# PCB_Schematic.net
KiCad netlist of a schematic drawn in EAGLE
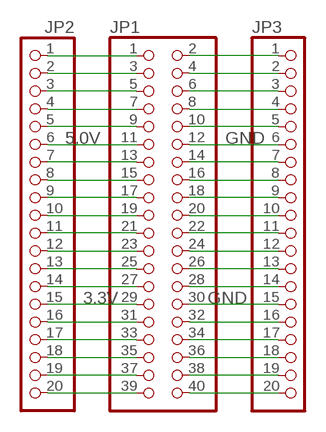
[diagram p0: schematic, sheet 1]

(export (version "E")
  (design (tool "Eeschema 10.0.6"))
  (components
    (comp (ref "JP1")
      (value "PINHD-2X20")
      (footprint "eagle-import:2X20")
      (libsource (lib "eagle-import") (part "PINHD-2X20"))
    )
    (comp (ref "JP2")
      (value "PINHD-1X20")
      (footprint "eagle-import:1X20")
      (libsource (lib "eagle-import") (part "PINHD-1X20"))
    )
    (comp (ref "JP3")
      (value "PINHD-1X20")
      (footprint "eagle-import:1X20")
      (libsource (lib "eagle-import") (part "PINHD-1X20"))
    )
  )
  (nets
    (net (code "1") (name "/3.3V") (class "Default")
      (node (ref "JP1") (pin "29") (pinfunction "29_29") (pintype "passive"))
      (node (ref "JP2") (pin "15") (pinfunction "15_15") (pintype "passive"))
    )
    (net (code "2") (name "/5.0V") (class "Default")
      (node (ref "JP1") (pin "11") (pinfunction "11_11") (pintype "passive"))
      (node (ref "JP2") (pin "6") (pinfunction "6_6") (pintype "passive"))
    )
    (net (code "3") (name "/GND") (class "Default")
      (node (ref "JP1") (pin "12") (pinfunction "12_12") (pintype "passive"))
      (node (ref "JP1") (pin "30") (pinfunction "30_30") (pintype "passive"))
      (node (ref "JP3") (pin "15") (pinfunction "15_15") (pintype "passive"))
      (node (ref "JP3") (pin "6") (pinfunction "6_6") (pintype "passive"))
    )
    (net (code "4") (name "Net-(JP1-Pad1)") (class "Default")
      (node (ref "JP1") (pin "1") (pinfunction "1_1") (pintype "passive"))
      (node (ref "JP2") (pin "1") (pinfunction "1_1") (pintype "passive"))
    )
    (net (code "5") (name "Net-(JP1-Pad2)") (class "Default")
      (node (ref "JP1") (pin "2") (pinfunction "2_2") (pintype "passive"))
      (node (ref "JP3") (pin "1") (pinfunction "1_1") (pintype "passive"))
    )
    (net (code "6") (name "Net-(JP1-Pad3)") (class "Default")
      (node (ref "JP1") (pin "3") (pinfunction "3_3") (pintype "passive"))
      (node (ref "JP2") (pin "2") (pinfunction "2_2") (pintype "passive"))
    )
    (net (code "7") (name "Net-(JP1-Pad4)") (class "Default")
      (node (ref "JP1") (pin "4") (pinfunction "4_4") (pintype "passive"))
      (node (ref "JP3") (pin "2") (pinfunction "2_2") (pintype "passive"))
    )
    (net (code "8") (name "Net-(JP1-Pad5)") (class "Default")
      (node (ref "JP1") (pin "5") (pinfunction "5_5") (pintype "passive"))
      (node (ref "JP2") (pin "3") (pinfunction "3_3") (pintype "passive"))
    )
    (net (code "9") (name "Net-(JP1-Pad6)") (class "Default")
      (node (ref "JP1") (pin "6") (pinfunction "6_6") (pintype "passive"))
      (node (ref "JP3") (pin "3") (pinfunction "3_3") (pintype "passive"))
    )
    (net (code "10") (name "Net-(JP1-Pad7)") (class "Default")
      (node (ref "JP1") (pin "7") (pinfunction "7_7") (pintype "passive"))
      (node (ref "JP2") (pin "4") (pinfunction "4_4") (pintype "passive"))
    )
    (net (code "11") (name "Net-(JP1-Pad8)") (class "Default")
      (node (ref "JP1") (pin "8") (pinfunction "8_8") (pintype "passive"))
      (node (ref "JP3") (pin "4") (pinfunction "4_4") (pintype "passive"))
    )
    (net (code "12") (name "Net-(JP1-Pad9)") (class "Default")
      (node (ref "JP1") (pin "9") (pinfunction "9_9") (pintype "passive"))
      (node (ref "JP2") (pin "5") (pinfunction "5_5") (pintype "passive"))
    )
    (net (code "13") (name "Net-(JP1-Pad10)") (class "Default")
      (node (ref "JP1") (pin "10") (pinfunction "10_10") (pintype "passive"))
      (node (ref "JP3") (pin "5") (pinfunction "5_5") (pintype "passive"))
    )
    (net (code "14") (name "Net-(JP1-Pad13)") (class "Default")
      (node (ref "JP1") (pin "13") (pinfunction "13_13") (pintype "passive"))
      (node (ref "JP2") (pin "7") (pinfunction "7_7") (pintype "passive"))
    )
    (net (code "15") (name "Net-(JP1-Pad14)") (class "Default")
      (node (ref "JP1") (pin "14") (pinfunction "14_14") (pintype "passive"))
      (node (ref "JP3") (pin "7") (pinfunction "7_7") (pintype "passive"))
    )
    (net (code "16") (name "Net-(JP1-Pad15)") (class "Default")
      (node (ref "JP1") (pin "15") (pinfunction "15_15") (pintype "passive"))
      (node (ref "JP2") (pin "8") (pinfunction "8_8") (pintype "passive"))
    )
    (net (code "17") (name "Net-(JP1-Pad16)") (class "Default")
      (node (ref "JP1") (pin "16") (pinfunction "16_16") (pintype "passive"))
      (node (ref "JP3") (pin "8") (pinfunction "8_8") (pintype "passive"))
    )
    (net (code "18") (name "Net-(JP1-Pad17)") (class "Default")
      (node (ref "JP1") (pin "17") (pinfunction "17_17") (pintype "passive"))
      (node (ref "JP2") (pin "9") (pinfunction "9_9") (pintype "passive"))
    )
    (net (code "19") (name "Net-(JP1-Pad18)") (class "Default")
      (node (ref "JP1") (pin "18") (pinfunction "18_18") (pintype "passive"))
      (node (ref "JP3") (pin "9") (pinfunction "9_9") (pintype "passive"))
    )
    (net (code "20") (name "Net-(JP1-Pad19)") (class "Default")
      (node (ref "JP1") (pin "19") (pinfunction "19_19") (pintype "passive"))
      (node (ref "JP2") (pin "10") (pinfunction "10_10") (pintype "passive"))
    )
    (net (code "21") (name "Net-(JP1-Pad20)") (class "Default")
      (node (ref "JP1") (pin "20") (pinfunction "20_20") (pintype "passive"))
      (node (ref "JP3") (pin "10") (pinfunction "10_10") (pintype "passive"))
    )
    (net (code "22") (name "Net-(JP1-Pad21)") (class "Default")
      (node (ref "JP1") (pin "21") (pinfunction "21_21") (pintype "passive"))
      (node (ref "JP2") (pin "11") (pinfunction "11_11") (pintype "passive"))
    )
    (net (code "23") (name "Net-(JP1-Pad22)") (class "Default")
      (node (ref "JP1") (pin "22") (pinfunction "22_22") (pintype "passive"))
      (node (ref "JP3") (pin "11") (pinfunction "11_11") (pintype "passive"))
    )
    (net (code "24") (name "Net-(JP1-Pad23)") (class "Default")
      (node (ref "JP1") (pin "23") (pinfunction "23_23") (pintype "passive"))
      (node (ref "JP2") (pin "12") (pinfunction "12_12") (pintype "passive"))
    )
    (net (code "25") (name "Net-(JP1-Pad24)") (class "Default")
      (node (ref "JP1") (pin "24") (pinfunction "24_24") (pintype "passive"))
      (node (ref "JP3") (pin "12") (pinfunction "12_12") (pintype "passive"))
    )
    (net (code "26") (name "Net-(JP1-Pad25)") (class "Default")
      (node (ref "JP1") (pin "25") (pinfunction "25_25") (pintype "passive"))
      (node (ref "JP2") (pin "13") (pinfunction "13_13") (pintype "passive"))
    )
    (net (code "27") (name "Net-(JP1-Pad26)") (class "Default")
      (node (ref "JP1") (pin "26") (pinfunction "26_26") (pintype "passive"))
      (node (ref "JP3") (pin "13") (pinfunction "13_13") (pintype "passive"))
    )
    (net (code "28") (name "Net-(JP1-Pad27)") (class "Default")
      (node (ref "JP1") (pin "27") (pinfunction "27_27") (pintype "passive"))
      (node (ref "JP2") (pin "14") (pinfunction "14_14") (pintype "passive"))
    )
    (net (code "29") (name "Net-(JP1-Pad28)") (class "Default")
      (node (ref "JP1") (pin "28") (pinfunction "28_28") (pintype "passive"))
      (node (ref "JP3") (pin "14") (pinfunction "14_14") (pintype "passive"))
    )
    (net (code "30") (name "Net-(JP1-Pad31)") (class "Default")
      (node (ref "JP1") (pin "31") (pinfunction "31_31") (pintype "passive"))
      (node (ref "JP2") (pin "16") (pinfunction "16_16") (pintype "passive"))
    )
    (net (code "31") (name "Net-(JP1-Pad32)") (class "Default")
      (node (ref "JP1") (pin "32") (pinfunction "32_32") (pintype "passive"))
      (node (ref "JP3") (pin "16") (pinfunction "16_16") (pintype "passive"))
    )
    (net (code "32") (name "Net-(JP1-Pad33)") (class "Default")
      (node (ref "JP1") (pin "33") (pinfunction "33_33") (pintype "passive"))
      (node (ref "JP2") (pin "17") (pinfunction "17_17") (pintype "passive"))
    )
    (net (code "33") (name "Net-(JP1-Pad34)") (class "Default")
      (node (ref "JP1") (pin "34") (pinfunction "34_34") (pintype "passive"))
      (node (ref "JP3") (pin "17") (pinfunction "17_17") (pintype "passive"))
    )
    (net (code "34") (name "Net-(JP1-Pad35)") (class "Default")
      (node (ref "JP1") (pin "35") (pinfunction "35_35") (pintype "passive"))
      (node (ref "JP2") (pin "18") (pinfunction "18_18") (pintype "passive"))
    )
    (net (code "35") (name "Net-(JP1-Pad36)") (class "Default")
      (node (ref "JP1") (pin "36") (pinfunction "36_36") (pintype "passive"))
      (node (ref "JP3") (pin "18") (pinfunction "18_18") (pintype "passive"))
    )
    (net (code "36") (name "Net-(JP1-Pad37)") (class "Default")
      (node (ref "JP1") (pin "37") (pinfunction "37_37") (pintype "passive"))
      (node (ref "JP2") (pin "19") (pinfunction "19_19") (pintype "passive"))
    )
    (net (code "37") (name "Net-(JP1-Pad38)") (class "Default")
      (node (ref "JP1") (pin "38") (pinfunction "38_38") (pintype "passive"))
      (node (ref "JP3") (pin "19") (pinfunction "19_19") (pintype "passive"))
    )
    (net (code "38") (name "Net-(JP1-Pad39)") (class "Default")
      (node (ref "JP1") (pin "39") (pinfunction "39_39") (pintype "passive"))
      (node (ref "JP2") (pin "20") (pinfunction "20_20") (pintype "passive"))
    )
    (net (code "39") (name "Net-(JP1-Pad40)") (class "Default")
      (node (ref "JP1") (pin "40") (pinfunction "40_40") (pintype "passive"))
      (node (ref "JP3") (pin "20") (pinfunction "20_20") (pintype "passive"))
    )
  )
)
